# VS1005BOB-Pico-LCD_2024-06-08.net
KiCad netlist of a schematic drawn in Altium Designer
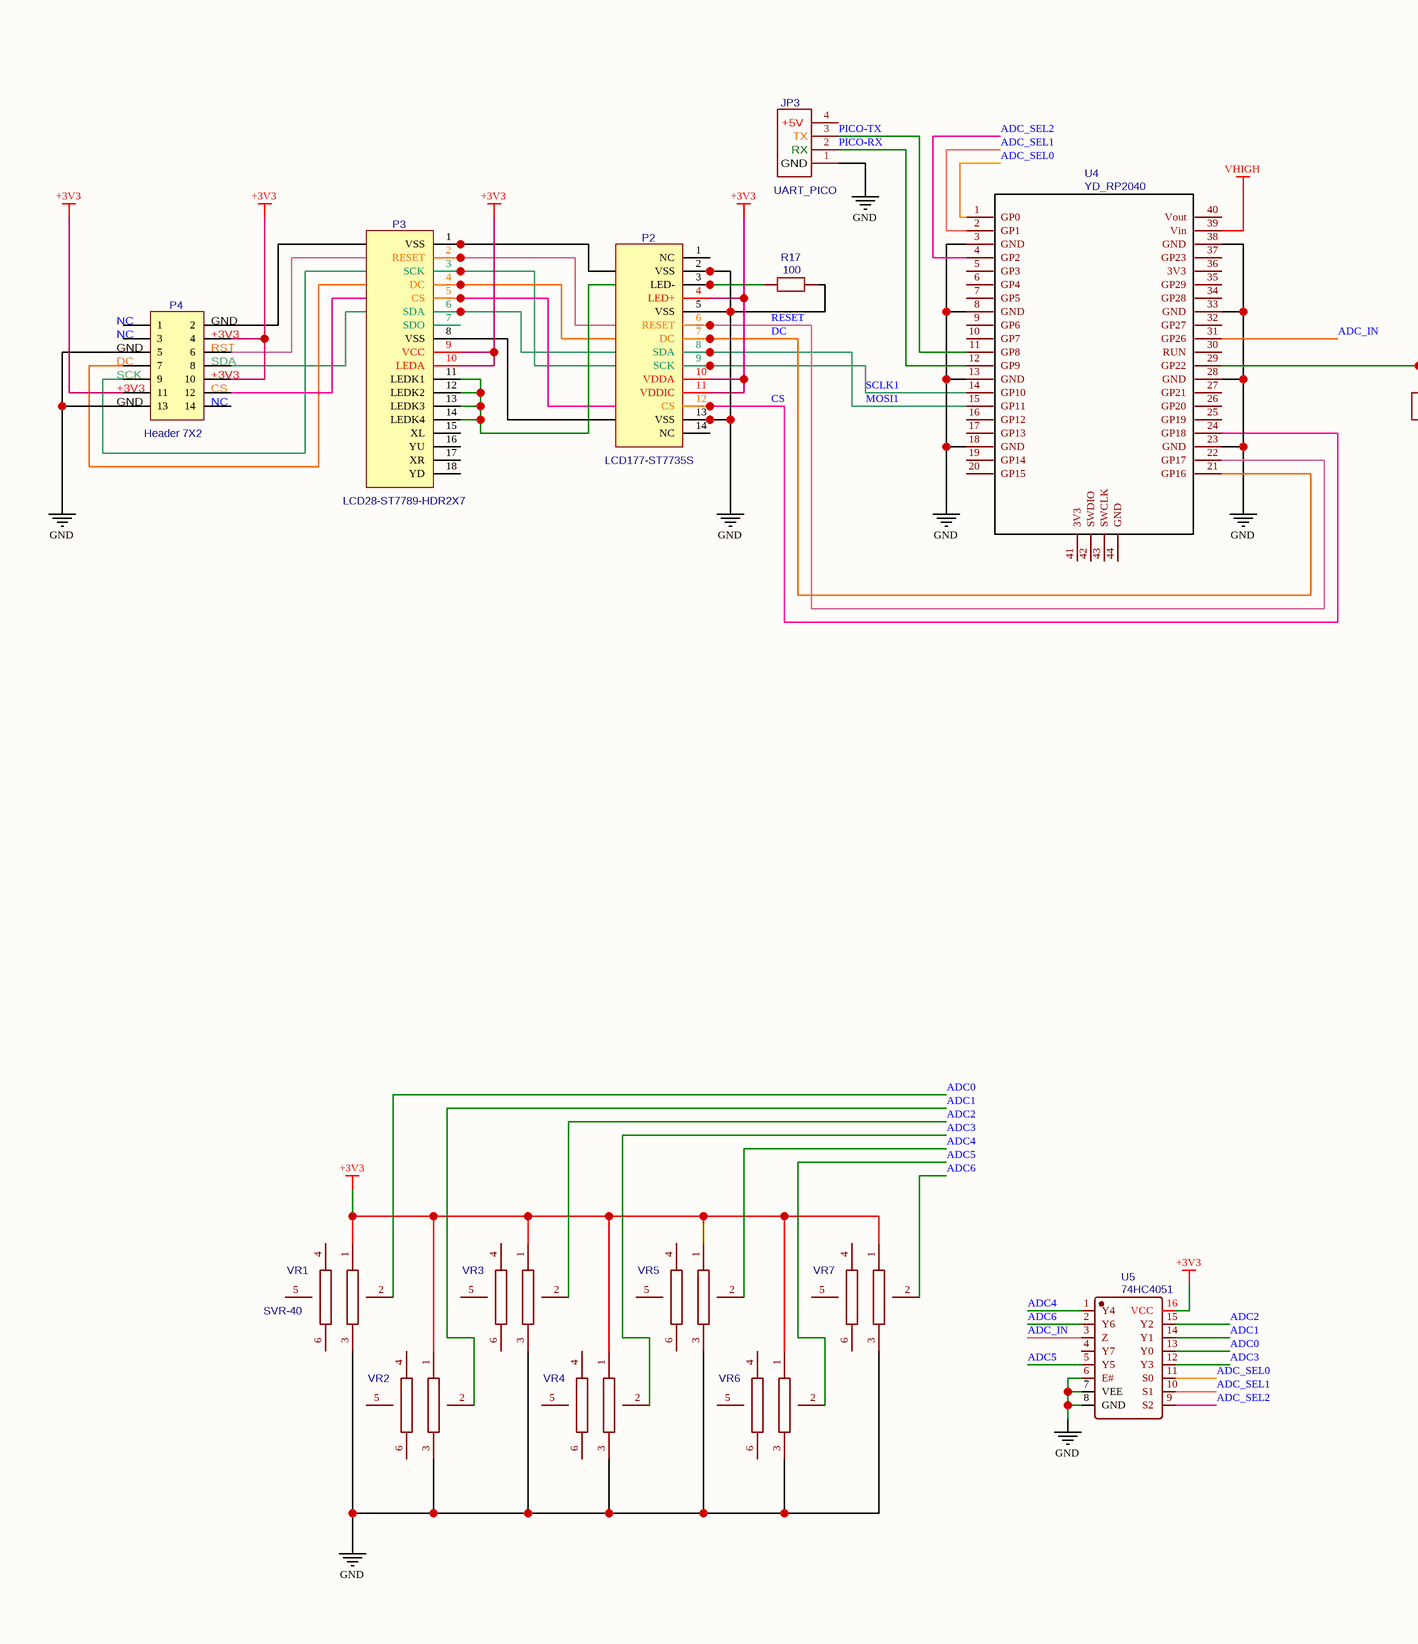
[diagram p0: VS1005BOB-Pico-LCD_2024-06-08.schdoc, left]
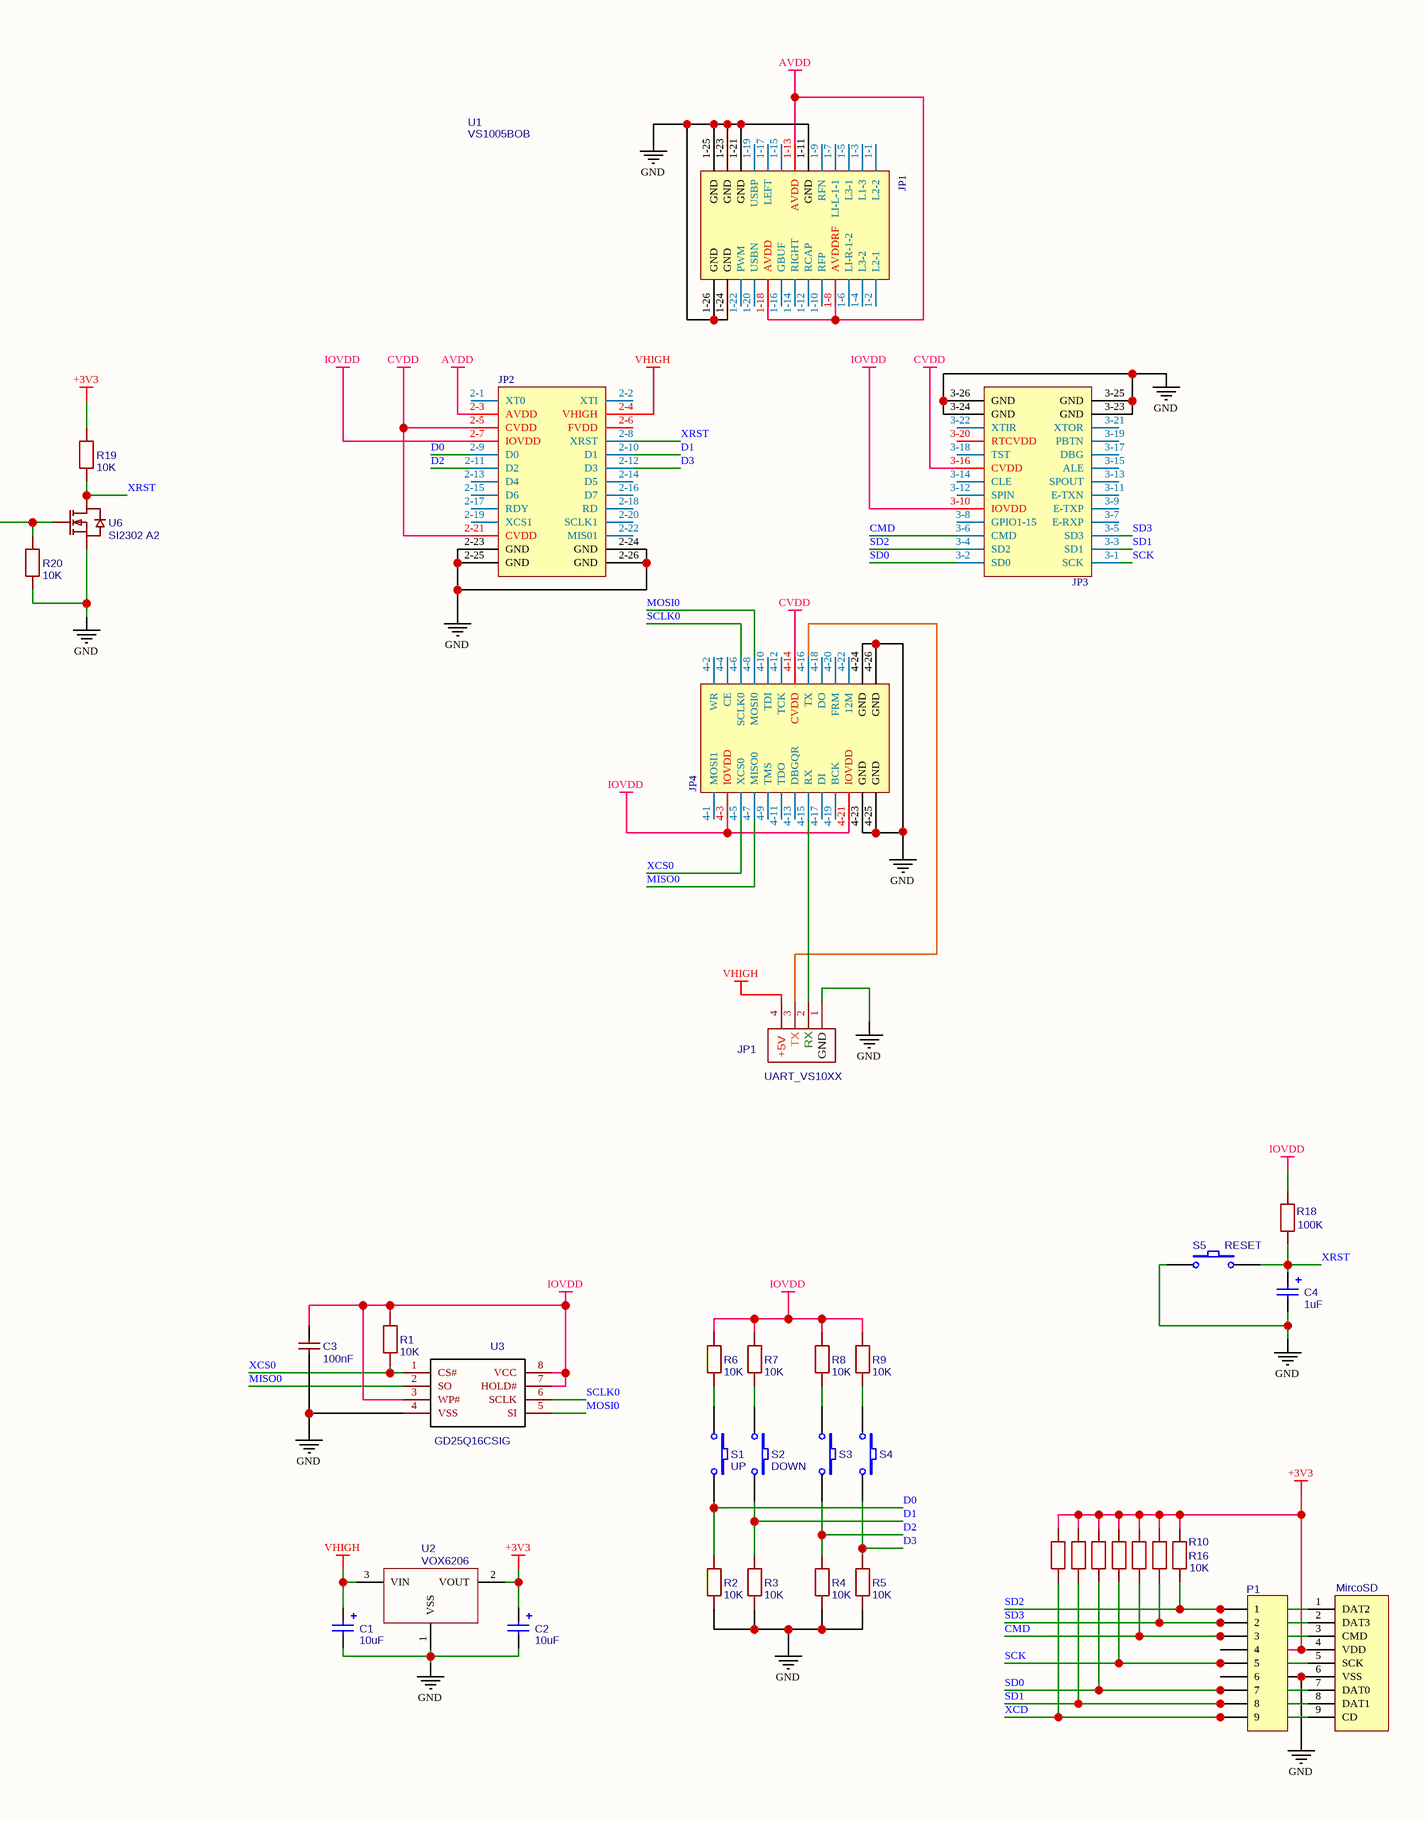
[diagram p1: VS1005BOB-Pico-LCD_2024-06-08.schdoc, right]

(export (version "E")
  (design (tool "Eeschema 10.0.6"))
  (components
    (comp (ref "C1")
      (value "10uF")
      (fields (field (name "PUBLISHER") "Altium Limited") (field (name "CONTRIBUTOR") "kmok163"))
      (libsource (lib "altium-import") (part "root_0_10uF_"))
    )
    (comp (ref "C2")
      (value "10uF")
      (fields (field (name "PUBLISHER") "Altium Limited") (field (name "CONTRIBUTOR") "kmok163"))
      (libsource (lib "altium-import") (part "root_0_10uF_"))
    )
    (comp (ref "C3")
      (value "100nF")
      (fields
        (field (name "MANUFACTURER PART") "CC0805KRX7R9BB104")
        (field (name "MANUFACTURER") "YAGEO")
        (field (name "CONTRIBUTOR") "fen-1")
      )
      (libsource (lib "altium-import") (part "root_3_100nF_"))
    )
    (comp (ref "C4")
      (value "1uF")
      (fields (field (name "PUBLISHER") "Altium Limited") (field (name "CONTRIBUTOR") "kmok163"))
      (libsource (lib "altium-import") (part "root_0_1uF_"))
    )
    (comp (ref "JP1")
      (value "UART_VS10XX")
      (description "Header 4")
      (fields (field (name "CONTRIBUTOR") "SparkFun"))
      (libsource (lib "altium-import") (part "root_1_UART_VS10XX_"))
    )
    (comp (ref "JP3")
      (value "UART_PICO")
      (description "Header 4")
      (fields (field (name "CONTRIBUTOR") "SparkFun"))
      (libsource (lib "altium-import") (part "root_0_UART_PICO_"))
    )
    (comp (ref "P1")
      (value "Header 9")
      (fields (field (name "PUBLISHER") "Altium Limited") (field (name "CONTRIBUTOR") "kmok163"))
      (libsource (lib "altium-import") (part "root_0_Header 9_"))
    )
    (comp (ref "P2")
      (value "LCD177-ST7735S")
      (fields (field (name "PUBLISHER") "Altium Limited") (field (name "CONTRIBUTOR") "kmok163"))
      (libsource (lib "altium-import") (part "root_0_LCD177-ST7735S_"))
    )
    (comp (ref "P3")
      (value "LCD28-ST7789-HDR2X7")
      (fields (field (name "PUBLISHER") "Altium Limited") (field (name "CONTRIBUTOR") "kmok163"))
      (libsource (lib "altium-import") (part "root_0_LCD28-ST7789-HDR2X7_"))
    )
    (comp (ref "P4")
      (value "Header 7X2")
      (fields (field (name "PUBLISHER") "Altium Limited") (field (name "CONTRIBUTOR") "lingtian"))
      (libsource (lib "altium-import") (part "root_0_Header 7X2_"))
    )
    (comp (ref "P6")
      (value "MircoSD")
      (fields (field (name "PUBLISHER") "Altium Limited") (field (name "CONTRIBUTOR") "kmok163"))
      (libsource (lib "altium-import") (part "root_0_MircoSD_"))
    )
    (comp (ref "R1")
      (value "10K")
      (fields (field (name "CONTRIBUTOR") "EDAUSER001"))
      (libsource (lib "altium-import") (part "root_1_10K_"))
    )
    (comp (ref "R2")
      (value "10K")
      (fields (field (name "CONTRIBUTOR") "EDAUSER001"))
      (libsource (lib "altium-import") (part "root_1_10K_"))
    )
    (comp (ref "R3")
      (value "10K")
      (fields (field (name "CONTRIBUTOR") "EDAUSER001"))
      (libsource (lib "altium-import") (part "root_1_10K_"))
    )
    (comp (ref "R4")
      (value "10K")
      (fields (field (name "CONTRIBUTOR") "EDAUSER001"))
      (libsource (lib "altium-import") (part "root_1_10K_"))
    )
    (comp (ref "R5")
      (value "10K")
      (fields (field (name "CONTRIBUTOR") "EDAUSER001"))
      (libsource (lib "altium-import") (part "root_1_10K_"))
    )
    (comp (ref "R6")
      (value "10K")
      (fields (field (name "CONTRIBUTOR") "EDAUSER001"))
      (libsource (lib "altium-import") (part "root_1_10K_"))
    )
    (comp (ref "R7")
      (value "10K")
      (fields (field (name "CONTRIBUTOR") "EDAUSER001"))
      (libsource (lib "altium-import") (part "root_1_10K_"))
    )
    (comp (ref "R8")
      (value "10K")
      (fields (field (name "CONTRIBUTOR") "EDAUSER001"))
      (libsource (lib "altium-import") (part "root_1_10K_"))
    )
    (comp (ref "R9")
      (value "10K")
      (fields (field (name "CONTRIBUTOR") "EDAUSER001"))
      (libsource (lib "altium-import") (part "root_1_10K_"))
    )
    (comp (ref "R10")
      (value "10K")
      (fields (field (name "CONTRIBUTOR") "EDAUSER001"))
      (libsource (lib "altium-import") (part "root_1_10K_"))
    )
    (comp (ref "R11")
      (value "10K")
      (fields (field (name "CONTRIBUTOR") "EDAUSER001"))
      (libsource (lib "altium-import") (part "root_1_10K_"))
    )
    (comp (ref "R12")
      (value "10K")
      (fields (field (name "CONTRIBUTOR") "EDAUSER001"))
      (libsource (lib "altium-import") (part "root_1_10K_"))
    )
    (comp (ref "R13")
      (value "10K")
      (fields (field (name "CONTRIBUTOR") "EDAUSER001"))
      (libsource (lib "altium-import") (part "root_1_10K_"))
    )
    (comp (ref "R14")
      (value "10K")
      (fields (field (name "CONTRIBUTOR") "EDAUSER001"))
      (libsource (lib "altium-import") (part "root_1_10K_"))
    )
    (comp (ref "R15")
      (value "10K")
      (fields (field (name "CONTRIBUTOR") "EDAUSER001"))
      (libsource (lib "altium-import") (part "root_1_10K_"))
    )
    (comp (ref "R16")
      (value "10K")
      (fields (field (name "CONTRIBUTOR") "EDAUSER001"))
      (libsource (lib "altium-import") (part "root_1_10K_"))
    )
    (comp (ref "R17")
      (value "100")
      (fields (field (name "CONTRIBUTOR") "EDAUSER001"))
      (libsource (lib "altium-import") (part "root_0_100_"))
    )
    (comp (ref "R18")
      (value "100K")
      (fields (field (name "CONTRIBUTOR") "EDAUSER001"))
      (libsource (lib "altium-import") (part "root_1_100K_"))
    )
    (comp (ref "R19")
      (value "10K")
      (fields (field (name "CONTRIBUTOR") "EDAUSER001"))
      (libsource (lib "altium-import") (part "root_1_10K_"))
    )
    (comp (ref "R20")
      (value "10K")
      (fields (field (name "CONTRIBUTOR") "EDAUSER001"))
      (libsource (lib "altium-import") (part "root_1_10K_"))
    )
    (comp (ref "S1")
      (value "UP")
      (fields (field (name "PUBLISHER") "Altium Limited") (field (name "CONTRIBUTOR") "kmok163"))
      (libsource (lib "altium-import") (part "root_3_UP_"))
    )
    (comp (ref "S2")
      (value "DOWN")
      (fields (field (name "PUBLISHER") "Altium Limited") (field (name "CONTRIBUTOR") "kmok163"))
      (libsource (lib "altium-import") (part "root_3_DOWN_"))
    )
    (comp (ref "S3")
      (value "D2")
      (fields (field (name "PUBLISHER") "Altium Limited") (field (name "CONTRIBUTOR") "kmok163"))
      (libsource (lib "altium-import") (part "root_3_D2_"))
    )
    (comp (ref "S4")
      (value "D3")
      (fields (field (name "PUBLISHER") "Altium Limited") (field (name "CONTRIBUTOR") "kmok163"))
      (libsource (lib "altium-import") (part "root_3_D3_"))
    )
    (comp (ref "S5")
      (value "RESET")
      (fields (field (name "PUBLISHER") "Altium Limited") (field (name "CONTRIBUTOR") "kmok163"))
      (libsource (lib "altium-import") (part "root_0_RESET_"))
    )
    (comp (ref "U1")
      (value "VS1005BOB")
      (fields (field (name "MANUFACTURER") "VLSI Solution Oy") (field (name "CONTRIBUTOR") "kmok163"))
      (libsource (lib "altium-import") (part "root_0_VS1005BOB_"))
    )
    (comp (ref "U2")
      (value "VOX6206")
      (fields (field (name "PUBLISHER") "Altium Limited") (field (name "CONTRIBUTOR") "kmok163"))
      (libsource (lib "altium-import") (part "root_0_VOX6206_"))
    )
    (comp (ref "U3")
      (value "GD25Q16CSIG")
      (fields (field (name "MANUFACTURER") "GigaDevice(兆易创新)"))
      (libsource (lib "altium-import") (part "root_0_GD25Q16CSIG_"))
    )
    (comp (ref "U4")
      (value "YD_RP2040")
      (fields (field (name "CONTRIBUTOR") "armxu"))
      (libsource (lib "altium-import") (part "root_0_YD_RP2040_"))
    )
    (comp (ref "U5")
      (value "74HC4051")
      (fields (field (name "MANUFACTURER") "I-CORE(中微爱芯)") (field (name "CONTRIBUTOR") "lcsc"))
      (libsource (lib "altium-import") (part "root_0_74HC4051_"))
    )
    (comp (ref "U6")
      (value "SI2302 A2")
      (fields (field (name "MANUFACTURER") "YONGYUTAI(永裕泰)") (field (name "CONTRIBUTOR") "lcsc"))
      (libsource (lib "altium-import") (part "root_0_SI2302 A2_"))
    )
    (comp (ref "VR1")
      (value "SVR-40")
      (fields
        (field (name "MANUFACTURER") "联合科技")
        (field (name "MANUFACTURER PART") "VVR-40-100KB")
        (field (name "CONTRIBUTOR") "kmok163")
      )
      (libsource (lib "altium-import") (part "root_0_SVR-40_"))
    )
    (comp (ref "VR2")
      (value "SVR-40")
      (fields
        (field (name "MANUFACTURER") "联合科技")
        (field (name "MANUFACTURER PART") "VVR-40-100KB")
        (field (name "CONTRIBUTOR") "kmok163")
      )
      (libsource (lib "altium-import") (part "root_0_SVR-40_"))
    )
    (comp (ref "VR3")
      (value "SVR-40")
      (fields
        (field (name "MANUFACTURER") "联合科技")
        (field (name "MANUFACTURER PART") "VVR-40-100KB")
        (field (name "CONTRIBUTOR") "kmok163")
      )
      (libsource (lib "altium-import") (part "root_0_SVR-40_"))
    )
    (comp (ref "VR4")
      (value "SVR-40")
      (fields
        (field (name "MANUFACTURER") "联合科技")
        (field (name "MANUFACTURER PART") "VVR-40-100KB")
        (field (name "CONTRIBUTOR") "kmok163")
      )
      (libsource (lib "altium-import") (part "root_0_SVR-40_"))
    )
    (comp (ref "VR5")
      (value "SVR-40")
      (fields
        (field (name "MANUFACTURER") "联合科技")
        (field (name "MANUFACTURER PART") "VVR-40-100KB")
        (field (name "CONTRIBUTOR") "kmok163")
      )
      (libsource (lib "altium-import") (part "root_0_SVR-40_"))
    )
    (comp (ref "VR6")
      (value "SVR-40")
      (fields
        (field (name "MANUFACTURER") "联合科技")
        (field (name "MANUFACTURER PART") "VVR-40-100KB")
        (field (name "CONTRIBUTOR") "kmok163")
      )
      (libsource (lib "altium-import") (part "root_0_SVR-40_"))
    )
    (comp (ref "VR7")
      (value "SVR-40")
      (fields
        (field (name "MANUFACTURER") "联合科技")
        (field (name "MANUFACTURER PART") "VVR-40-100KB")
        (field (name "CONTRIBUTOR") "kmok163")
      )
      (libsource (lib "altium-import") (part "root_0_SVR-40_"))
    )
  )
  (nets
    (net (code "1") (name "+3V3") (class "Default")
      (node (ref "C2") (pin "1") (pinfunction "1_1") (pintype "passive"))
      (node (ref "P1") (pin "4") (pinfunction "4_4") (pintype "passive"))
      (node (ref "P2") (pin "10") (pinfunction "VDDA_10") (pintype "passive"))
      (node (ref "P2") (pin "11") (pinfunction "VDDIC_11") (pintype "passive"))
      (node (ref "P2") (pin "4") (pinfunction "LED+_4") (pintype "passive"))
      (node (ref "P3") (pin "10") (pinfunction "LEDA_10") (pintype "passive"))
      (node (ref "P3") (pin "9") (pinfunction "VCC_9") (pintype "passive"))
      (node (ref "P4") (pin "10") (pinfunction "10_10") (pintype "passive"))
      (node (ref "P4") (pin "11") (pinfunction "11_11") (pintype "passive"))
      (node (ref "P4") (pin "4") (pinfunction "4_4") (pintype "passive"))
      (node (ref "P6") (pin "4") (pinfunction "VDD_4") (pintype "passive"))
      (node (ref "R10") (pin "2") (pinfunction "2_2") (pintype "passive"))
      (node (ref "R11") (pin "2") (pinfunction "2_2") (pintype "passive"))
      (node (ref "R12") (pin "2") (pinfunction "2_2") (pintype "passive"))
      (node (ref "R13") (pin "2") (pinfunction "2_2") (pintype "passive"))
      (node (ref "R14") (pin "2") (pinfunction "2_2") (pintype "passive"))
      (node (ref "R15") (pin "2") (pinfunction "2_2") (pintype "passive"))
      (node (ref "R16") (pin "2") (pinfunction "2_2") (pintype "passive"))
      (node (ref "R19") (pin "2") (pinfunction "2_2") (pintype "passive"))
      (node (ref "U2") (pin "2") (pinfunction "VOUT_2") (pintype "passive"))
      (node (ref "U5") (pin "16") (pinfunction "VCC_16") (pintype "passive"))
      (node (ref "VR1") (pin "1") (pinfunction "1_1") (pintype "passive"))
      (node (ref "VR2") (pin "1") (pinfunction "1_1") (pintype "passive"))
      (node (ref "VR3") (pin "1") (pinfunction "1_1") (pintype "passive"))
      (node (ref "VR4") (pin "1") (pinfunction "1_1") (pintype "passive"))
      (node (ref "VR5") (pin "1") (pinfunction "1_1") (pintype "passive"))
      (node (ref "VR6") (pin "1") (pinfunction "1_1") (pintype "passive"))
      (node (ref "VR7") (pin "1") (pinfunction "1_1") (pintype "passive"))
    )
    (net (code "2") (name "/ADC0") (class "Default")
      (node (ref "U5") (pin "13") (pinfunction "Y0_13") (pintype "passive"))
      (node (ref "VR1") (pin "2") (pinfunction "2_2") (pintype "passive"))
    )
    (net (code "3") (name "/ADC1") (class "Default")
      (node (ref "U5") (pin "14") (pinfunction "Y1_14") (pintype "passive"))
      (node (ref "VR2") (pin "2") (pinfunction "2_2") (pintype "passive"))
    )
    (net (code "4") (name "/ADC2") (class "Default")
      (node (ref "U5") (pin "15") (pinfunction "Y2_15") (pintype "passive"))
      (node (ref "VR3") (pin "2") (pinfunction "2_2") (pintype "passive"))
    )
    (net (code "5") (name "/ADC3") (class "Default")
      (node (ref "U5") (pin "12") (pinfunction "Y3_12") (pintype "passive"))
      (node (ref "VR4") (pin "2") (pinfunction "2_2") (pintype "passive"))
    )
    (net (code "6") (name "/ADC4") (class "Default")
      (node (ref "U5") (pin "1") (pinfunction "Y4_1") (pintype "passive"))
      (node (ref "VR5") (pin "2") (pinfunction "2_2") (pintype "passive"))
    )
    (net (code "7") (name "/ADC5") (class "Default")
      (node (ref "U5") (pin "5") (pinfunction "Y5_5") (pintype "passive"))
      (node (ref "VR6") (pin "2") (pinfunction "2_2") (pintype "passive"))
    )
    (net (code "8") (name "/ADC6") (class "Default")
      (node (ref "U5") (pin "2") (pinfunction "Y6_2") (pintype "passive"))
      (node (ref "VR7") (pin "2") (pinfunction "2_2") (pintype "passive"))
    )
    (net (code "9") (name "/ADC_IN") (class "Default")
      (node (ref "U4") (pin "31") (pinfunction "GP26_31") (pintype "passive"))
      (node (ref "U5") (pin "3") (pinfunction "Z_3") (pintype "passive"))
    )
    (net (code "10") (name "/ADC_SEL0") (class "Default")
      (node (ref "U4") (pin "1") (pinfunction "GP0_1") (pintype "passive"))
      (node (ref "U5") (pin "11") (pinfunction "S0_11") (pintype "passive"))
    )
    (net (code "11") (name "/ADC_SEL1") (class "Default")
      (node (ref "U4") (pin "2") (pinfunction "GP1_2") (pintype "passive"))
      (node (ref "U5") (pin "10") (pinfunction "S1_10") (pintype "passive"))
    )
    (net (code "12") (name "/ADC_SEL2") (class "Default")
      (node (ref "U4") (pin "4") (pinfunction "GP2_4") (pintype "passive"))
      (node (ref "U5") (pin "9") (pinfunction "S2_9") (pintype "passive"))
    )
    (net (code "13") (name "/CMD") (class "Default")
      (node (ref "P1") (pin "3") (pinfunction "3_3") (pintype "passive"))
      (node (ref "P6") (pin "3") (pinfunction "CMD_3") (pintype "passive"))
      (node (ref "R14") (pin "1") (pinfunction "1_1") (pintype "passive"))
      (node (ref "U1") (pin "3-6") (pinfunction "CMD_3-6") (pintype "passive"))
    )
    (net (code "14") (name "/CS") (class "Default")
      (node (ref "P2") (pin "12") (pinfunction "CS_12") (pintype "passive"))
      (node (ref "P3") (pin "5") (pinfunction "CS_5") (pintype "passive"))
      (node (ref "P4") (pin "12") (pinfunction "12_12") (pintype "passive"))
      (node (ref "U4") (pin "24") (pinfunction "GP18_24") (pintype "passive"))
    )
    (net (code "15") (name "/D0") (class "Default")
      (node (ref "R2") (pin "2") (pinfunction "2_2") (pintype "passive"))
      (node (ref "S1") (pin "2") (pinfunction "2_2") (pintype "passive"))
      (node (ref "U1") (pin "2-9") (pinfunction "D0_2-9") (pintype "passive"))
    )
    (net (code "16") (name "/D1") (class "Default")
      (node (ref "R3") (pin "2") (pinfunction "2_2") (pintype "passive"))
      (node (ref "S2") (pin "2") (pinfunction "2_2") (pintype "passive"))
      (node (ref "U1") (pin "2-10") (pinfunction "D1_2-10") (pintype "passive"))
    )
    (net (code "17") (name "/D2") (class "Default")
      (node (ref "R4") (pin "2") (pinfunction "2_2") (pintype "passive"))
      (node (ref "S3") (pin "2") (pinfunction "2_2") (pintype "passive"))
      (node (ref "U1") (pin "2-11") (pinfunction "D2_2-11") (pintype "passive"))
    )
    (net (code "18") (name "/D3") (class "Default")
      (node (ref "R5") (pin "2") (pinfunction "2_2") (pintype "passive"))
      (node (ref "S4") (pin "2") (pinfunction "2_2") (pintype "passive"))
      (node (ref "U1") (pin "2-12") (pinfunction "D3_2-12") (pintype "passive"))
    )
    (net (code "19") (name "/DC") (class "Default")
      (node (ref "P2") (pin "7") (pinfunction "DC_7") (pintype "passive"))
      (node (ref "P3") (pin "4") (pinfunction "DC_4") (pintype "passive"))
      (node (ref "P4") (pin "7") (pinfunction "7_7") (pintype "passive"))
      (node (ref "U4") (pin "21") (pinfunction "GP16_21") (pintype "passive"))
    )
    (net (code "20") (name "/MISO0") (class "Default")
      (node (ref "U1") (pin "4-7") (pinfunction "MISO0_4-7") (pintype "passive"))
      (node (ref "U3") (pin "2") (pinfunction "SO_2") (pintype "passive"))
    )
    (net (code "21") (name "/MOSI0") (class "Default")
      (node (ref "U1") (pin "4-8") (pinfunction "MOSI0_4-8") (pintype "passive"))
      (node (ref "U3") (pin "5") (pinfunction "SI_5") (pintype "passive"))
    )
    (net (code "22") (name "/MOSI1") (class "Default")
      (node (ref "P2") (pin "8") (pinfunction "SDA_8") (pintype "passive"))
      (node (ref "P3") (pin "6") (pinfunction "SDA_6") (pintype "passive"))
      (node (ref "P4") (pin "8") (pinfunction "8_8") (pintype "passive"))
      (node (ref "U4") (pin "15") (pinfunction "GP11_15") (pintype "passive"))
    )
    (net (code "23") (name "/PICO-RX") (class "Default")
      (node (ref "JP3") (pin "2") (pinfunction "2_2") (pintype "passive"))
      (node (ref "U4") (pin "12") (pinfunction "GP9_12") (pintype "passive"))
    )
    (net (code "24") (name "/PICO-TX") (class "Default")
      (node (ref "JP3") (pin "3") (pinfunction "3_3") (pintype "passive"))
      (node (ref "U4") (pin "11") (pinfunction "GP8_11") (pintype "passive"))
    )
    (net (code "25") (name "/RESET") (class "Default")
      (node (ref "P2") (pin "6") (pinfunction "RESET_6") (pintype "passive"))
      (node (ref "P3") (pin "2") (pinfunction "RESET_2") (pintype "passive"))
      (node (ref "P4") (pin "6") (pinfunction "6_6") (pintype "passive"))
      (node (ref "U4") (pin "22") (pinfunction "GP17_22") (pintype "passive"))
    )
    (net (code "26") (name "/SCK") (class "Default")
      (node (ref "P1") (pin "5") (pinfunction "5_5") (pintype "passive"))
      (node (ref "P6") (pin "5") (pinfunction "SCK_5") (pintype "passive"))
      (node (ref "R13") (pin "1") (pinfunction "1_1") (pintype "passive"))
      (node (ref "U1") (pin "3-1") (pinfunction "SCK_3-1") (pintype "passive"))
    )
    (net (code "27") (name "/SCLK0") (class "Default")
      (node (ref "U1") (pin "4-6") (pinfunction "SCLK0_4-6") (pintype "passive"))
      (node (ref "U3") (pin "6") (pinfunction "SCLK_6") (pintype "passive"))
    )
    (net (code "28") (name "/SCLK1") (class "Default")
      (node (ref "P2") (pin "9") (pinfunction "SCK_9") (pintype "passive"))
      (node (ref "P3") (pin "3") (pinfunction "SCK_3") (pintype "passive"))
      (node (ref "P4") (pin "9") (pinfunction "9_9") (pintype "passive"))
      (node (ref "U4") (pin "14") (pinfunction "GP10_14") (pintype "passive"))
    )
    (net (code "29") (name "/SD0") (class "Default")
      (node (ref "P1") (pin "7") (pinfunction "7_7") (pintype "passive"))
      (node (ref "P6") (pin "7") (pinfunction "DAT0_7") (pintype "passive"))
      (node (ref "R12") (pin "1") (pinfunction "1_1") (pintype "passive"))
      (node (ref "U1") (pin "3-2") (pinfunction "SD0_3-2") (pintype "passive"))
    )
    (net (code "30") (name "/SD1") (class "Default")
      (node (ref "P1") (pin "8") (pinfunction "8_8") (pintype "passive"))
      (node (ref "P6") (pin "8") (pinfunction "DAT1_8") (pintype "passive"))
      (node (ref "R11") (pin "1") (pinfunction "1_1") (pintype "passive"))
      (node (ref "U1") (pin "3-3") (pinfunction "SD1_3-3") (pintype "passive"))
    )
    (net (code "31") (name "/SD2") (class "Default")
      (node (ref "P1") (pin "1") (pinfunction "1_1") (pintype "passive"))
      (node (ref "P6") (pin "1") (pinfunction "DAT2_1") (pintype "passive"))
      (node (ref "R16") (pin "1") (pinfunction "1_1") (pintype "passive"))
      (node (ref "U1") (pin "3-4") (pinfunction "SD2_3-4") (pintype "passive"))
    )
    (net (code "32") (name "/SD3") (class "Default")
      (node (ref "P1") (pin "2") (pinfunction "2_2") (pintype "passive"))
      (node (ref "P6") (pin "2") (pinfunction "DAT3_2") (pintype "passive"))
      (node (ref "R15") (pin "1") (pinfunction "1_1") (pintype "passive"))
      (node (ref "U1") (pin "3-5") (pinfunction "SD3_3-5") (pintype "passive"))
    )
    (net (code "33") (name "/XCD") (class "Default")
      (node (ref "P1") (pin "9") (pinfunction "9_9") (pintype "passive"))
      (node (ref "P6") (pin "9") (pinfunction "CD_9") (pintype "passive"))
      (node (ref "R10") (pin "1") (pinfunction "1_1") (pintype "passive"))
    )
    (net (code "34") (name "/XCS0") (class "Default")
      (node (ref "R1") (pin "1") (pinfunction "1_1") (pintype "passive"))
      (node (ref "U1") (pin "4-5") (pinfunction "XCS0_4-5") (pintype "passive"))
      (node (ref "U3") (pin "1") (pinfunction "CS#_1") (pintype "passive"))
    )
    (net (code "35") (name "/XRST") (class "Default")
      (node (ref "C4") (pin "1") (pinfunction "1_1") (pintype "passive"))
      (node (ref "R18") (pin "1") (pinfunction "1_1") (pintype "passive"))
      (node (ref "R19") (pin "1") (pinfunction "1_1") (pintype "passive"))
      (node (ref "S5") (pin "2") (pinfunction "2_2") (pintype "passive"))
      (node (ref "U1") (pin "2-8") (pinfunction "XRST_2-8") (pintype "passive"))
      (node (ref "U6") (pin "3") (pinfunction "D_3") (pintype "passive"))
    )
    (net (code "36") (name "AVDD") (class "Default")
      (node (ref "U1") (pin "1-13") (pinfunction "AVDD_1-13") (pintype "passive"))
      (node (ref "U1") (pin "1-18") (pinfunction "AVDD_1-18") (pintype "passive"))
      (node (ref "U1") (pin "1-8") (pinfunction "AVDDRF_1-8") (pintype "passive"))
      (node (ref "U1") (pin "2-3") (pinfunction "AVDD_2-3") (pintype "passive"))
    )
    (net (code "37") (name "CVDD") (class "Default")
      (node (ref "U1") (pin "2-21") (pinfunction "CVDD_2-21") (pintype "passive"))
      (node (ref "U1") (pin "2-5") (pinfunction "CVDD_2-5") (pintype "passive"))
      (node (ref "U1") (pin "3-16") (pinfunction "CVDD_3-16") (pintype "passive"))
      (node (ref "U1") (pin "4-14") (pinfunction "CVDD_4-14") (pintype "passive"))
    )
    (net (code "38") (name "GND") (class "Default")
      (node (ref "C1") (pin "2") (pinfunction "2_2") (pintype "passive"))
      (node (ref "C2") (pin "2") (pinfunction "2_2") (pintype "passive"))
      (node (ref "C3") (pin "2") (pinfunction "2_2") (pintype "passive"))
      (node (ref "C4") (pin "2") (pinfunction "2_2") (pintype "passive"))
      (node (ref "JP1") (pin "1") (pinfunction "1_1") (pintype "passive"))
      (node (ref "JP3") (pin "1") (pinfunction "1_1") (pintype "passive"))
      (node (ref "P1") (pin "6") (pinfunction "6_6") (pintype "passive"))
      (node (ref "P2") (pin "13") (pinfunction "VSS_13") (pintype "passive"))
      (node (ref "P2") (pin "2") (pinfunction "VSS_2") (pintype "passive"))
      (node (ref "P2") (pin "5") (pinfunction "VSS_5") (pintype "passive"))
      (node (ref "P3") (pin "1") (pinfunction "VSS_1") (pintype "passive"))
      (node (ref "P3") (pin "8") (pinfunction "VSS_8") (pintype "passive"))
      (node (ref "P4") (pin "13") (pinfunction "13_13") (pintype "passive"))
      (node (ref "P4") (pin "2") (pinfunction "2_2") (pintype "passive"))
      (node (ref "P4") (pin "5") (pinfunction "5_5") (pintype "passive"))
      (node (ref "P6") (pin "6") (pinfunction "VSS_6") (pintype "passive"))
      (node (ref "R17") (pin "1") (pinfunction "1_1") (pintype "passive"))
      (node (ref "R2") (pin "1") (pinfunction "1_1") (pintype "passive"))
      (node (ref "R20") (pin "1") (pinfunction "1_1") (pintype "passive"))
      (node (ref "R3") (pin "1") (pinfunction "1_1") (pintype "passive"))
      (node (ref "R4") (pin "1") (pinfunction "1_1") (pintype "passive"))
      (node (ref "R5") (pin "1") (pinfunction "1_1") (pintype "passive"))
      (node (ref "S5") (pin "1") (pinfunction "1_1") (pintype "passive"))
      (node (ref "U1") (pin "1-11") (pinfunction "GND_1-11") (pintype "passive"))
      (node (ref "U1") (pin "1-21") (pinfunction "GND_1-21") (pintype "passive"))
      (node (ref "U1") (pin "1-23") (pinfunction "GND_1-23") (pintype "passive"))
      (node (ref "U1") (pin "1-24") (pinfunction "GND_1-24") (pintype "passive"))
      (node (ref "U1") (pin "1-25") (pinfunction "GND_1-25") (pintype "passive"))
      (node (ref "U1") (pin "1-26") (pinfunction "GND_1-26") (pintype "passive"))
      (node (ref "U1") (pin "2-23") (pinfunction "GND_2-23") (pintype "passive"))
      (node (ref "U1") (pin "2-24") (pinfunction "GND_2-24") (pintype "passive"))
      (node (ref "U1") (pin "2-25") (pinfunction "GND_2-25") (pintype "passive"))
      (node (ref "U1") (pin "2-26") (pinfunction "GND_2-26") (pintype "passive"))
      (node (ref "U1") (pin "3-23") (pinfunction "GND_3-23") (pintype "passive"))
      (node (ref "U1") (pin "3-24") (pinfunction "GND_3-24") (pintype "passive"))
      (node (ref "U1") (pin "3-25") (pinfunction "GND_3-25") (pintype "passive"))
      (node (ref "U1") (pin "3-26") (pinfunction "GND_3-26") (pintype "passive"))
      (node (ref "U1") (pin "4-23") (pinfunction "GND_4-23") (pintype "passive"))
      (node (ref "U1") (pin "4-24") (pinfunction "GND_4-24") (pintype "passive"))
      (node (ref "U1") (pin "4-25") (pinfunction "GND_4-25") (pintype "passive"))
      (node (ref "U1") (pin "4-26") (pinfunction "GND_4-26") (pintype "passive"))
      (node (ref "U2") (pin "1") (pinfunction "VSS_1") (pintype "passive"))
      (node (ref "U3") (pin "4") (pinfunction "VSS_4") (pintype "passive"))
      (node (ref "U4") (pin "13") (pinfunction "GND_13") (pintype "passive"))
      (node (ref "U4") (pin "18") (pinfunction "GND_18") (pintype "passive"))
      (node (ref "U4") (pin "23") (pinfunction "GND_23") (pintype "passive"))
      (node (ref "U4") (pin "28") (pinfunction "GND_28") (pintype "passive"))
      (node (ref "U4") (pin "3") (pinfunction "GND_3") (pintype "passive"))
      (node (ref "U4") (pin "33") (pinfunction "GND_33") (pintype "passive"))
      (node (ref "U4") (pin "38") (pinfunction "GND_38") (pintype "passive"))
      (node (ref "U4") (pin "8") (pinfunction "GND_8") (pintype "passive"))
      (node (ref "U5") (pin "6") (pinfunction "E#_6") (pintype "passive"))
      (node (ref "U5") (pin "7") (pinfunction "VEE_7") (pintype "passive"))
      (node (ref "U5") (pin "8") (pinfunction "GND_8") (pintype "passive"))
      (node (ref "U6") (pin "2") (pinfunction "S_2") (pintype "passive"))
      (node (ref "VR1") (pin "3") (pinfunction "3_3") (pintype "passive"))
      (node (ref "VR2") (pin "3") (pinfunction "3_3") (pintype "passive"))
      (node (ref "VR3") (pin "3") (pinfunction "3_3") (pintype "passive"))
      (node (ref "VR4") (pin "3") (pinfunction "3_3") (pintype "passive"))
      (node (ref "VR5") (pin "3") (pinfunction "3_3") (pintype "passive"))
      (node (ref "VR6") (pin "3") (pinfunction "3_3") (pintype "passive"))
      (node (ref "VR7") (pin "3") (pinfunction "3_3") (pintype "passive"))
    )
    (net (code "39") (name "IOVDD") (class "Default")
      (node (ref "C3") (pin "1") (pinfunction "1_1") (pintype "passive"))
      (node (ref "R1") (pin "2") (pinfunction "2_2") (pintype "passive"))
      (node (ref "R18") (pin "2") (pinfunction "2_2") (pintype "passive"))
      (node (ref "R6") (pin "2") (pinfunction "2_2") (pintype "passive"))
      (node (ref "R7") (pin "2") (pinfunction "2_2") (pintype "passive"))
      (node (ref "R8") (pin "2") (pinfunction "2_2") (pintype "passive"))
      (node (ref "R9") (pin "2") (pinfunction "2_2") (pintype "passive"))
      (node (ref "U1") (pin "2-7") (pinfunction "IOVDD_2-7") (pintype "passive"))
      (node (ref "U1") (pin "3-10") (pinfunction "IOVDD_3-10") (pintype "passive"))
      (node (ref "U1") (pin "4-21") (pinfunction "IOVDD_4-21") (pintype "passive"))
      (node (ref "U1") (pin "4-3") (pinfunction "IOVDD_4-3") (pintype "passive"))
      (node (ref "U3") (pin "3") (pinfunction "WP#_3") (pintype "passive"))
      (node (ref "U3") (pin "7") (pinfunction "HOLD#_7") (pintype "passive"))
      (node (ref "U3") (pin "8") (pinfunction "VCC_8") (pintype "passive"))
    )
    (net (code "40") (name "Net-(P2-LED-)") (class "Default")
      (node (ref "P2") (pin "3") (pinfunction "LED-_3") (pintype "passive"))
      (node (ref "P3") (pin "11") (pinfunction "LEDK1_11") (pintype "passive"))
      (node (ref "P3") (pin "12") (pinfunction "LEDK2_12") (pintype "passive"))
      (node (ref "P3") (pin "13") (pinfunction "LEDK3_13") (pintype "passive"))
      (node (ref "P3") (pin "14") (pinfunction "LEDK4_14") (pintype "passive"))
      (node (ref "R17") (pin "2") (pinfunction "2_2") (pintype "passive"))
    )
    (net (code "41") (name "Net-(R6-Pad1)") (class "Default")
      (node (ref "R6") (pin "1") (pinfunction "1_1") (pintype "passive"))
      (node (ref "S1") (pin "1") (pinfunction "1_1") (pintype "passive"))
    )
    (net (code "42") (name "Net-(R7-Pad1)") (class "Default")
      (node (ref "R7") (pin "1") (pinfunction "1_1") (pintype "passive"))
      (node (ref "S2") (pin "1") (pinfunction "1_1") (pintype "passive"))
    )
    (net (code "43") (name "Net-(R8-Pad1)") (class "Default")
      (node (ref "R8") (pin "1") (pinfunction "1_1") (pintype "passive"))
      (node (ref "S3") (pin "1") (pinfunction "1_1") (pintype "passive"))
    )
    (net (code "44") (name "Net-(R9-Pad1)") (class "Default")
      (node (ref "R9") (pin "1") (pinfunction "1_1") (pintype "passive"))
      (node (ref "S4") (pin "1") (pinfunction "1_1") (pintype "passive"))
    )
    (net (code "45") (name "Net-(U1-RX)") (class "Default")
      (node (ref "JP1") (pin "2") (pinfunction "2_2") (pintype "passive"))
      (node (ref "U1") (pin "4-15") (pinfunction "RX_4-15") (pintype "passive"))
    )
    (net (code "46") (name "Net-(U1-TX)") (class "Default")
      (node (ref "JP1") (pin "3") (pinfunction "3_3") (pintype "passive"))
      (node (ref "U1") (pin "4-16") (pinfunction "TX_4-16") (pintype "passive"))
    )
    (net (code "47") (name "Net-(U4-GP22)") (class "Default")
      (node (ref "R20") (pin "2") (pinfunction "2_2") (pintype "passive"))
      (node (ref "U4") (pin "29") (pinfunction "GP22_29") (pintype "passive"))
      (node (ref "U6") (pin "1") (pinfunction "G_1") (pintype "passive"))
    )
    (net (code "48") (name "VHIGH") (class "Default")
      (node (ref "C1") (pin "1") (pinfunction "1_1") (pintype "passive"))
      (node (ref "JP1") (pin "4") (pinfunction "4_4") (pintype "passive"))
      (node (ref "U1") (pin "2-4") (pinfunction "VHIGH_2-4") (pintype "passive"))
      (node (ref "U2") (pin "3") (pinfunction "VIN_3") (pintype "passive"))
      (node (ref "U4") (pin "39") (pinfunction "Vin_39") (pintype "passive"))
    )
    (net (code "49") (name "unconnected-(JP3-Pad4)") (class "Default")
      (node (ref "JP3") (pin "4") (pinfunction "4_4") (pintype "passive"))
    )
    (net (code "50") (name "unconnected-(P2-NC-Pad1)") (class "Default")
      (node (ref "P2") (pin "1") (pinfunction "NC_1") (pintype "passive"))
    )
    (net (code "51") (name "unconnected-(P2-NC-Pad14)") (class "Default")
      (node (ref "P2") (pin "14") (pinfunction "NC_14") (pintype "passive"))
    )
    (net (code "52") (name "unconnected-(P3-SDO-Pad7)") (class "Default")
      (node (ref "P3") (pin "7") (pinfunction "SDO_7") (pintype "passive"))
    )
    (net (code "53") (name "unconnected-(P3-XL-Pad15)") (class "Default")
      (node (ref "P3") (pin "15") (pinfunction "XL_15") (pintype "passive"))
    )
    (net (code "54") (name "unconnected-(P3-XR-Pad17)") (class "Default")
      (node (ref "P3") (pin "17") (pinfunction "XR_17") (pintype "passive"))
    )
    (net (code "55") (name "unconnected-(P3-YD-Pad18)") (class "Default")
      (node (ref "P3") (pin "18") (pinfunction "YD_18") (pintype "passive"))
    )
    (net (code "56") (name "unconnected-(P3-YU-Pad16)") (class "Default")
      (node (ref "P3") (pin "16") (pinfunction "YU_16") (pintype "passive"))
    )
    (net (code "57") (name "unconnected-(P4-Pad1)") (class "Default")
      (node (ref "P4") (pin "1") (pinfunction "1_1") (pintype "passive"))
    )
    (net (code "58") (name "unconnected-(P4-Pad3)") (class "Default")
      (node (ref "P4") (pin "3") (pinfunction "3_3") (pintype "passive"))
    )
    (net (code "59") (name "unconnected-(P4-Pad14)") (class "Default")
      (node (ref "P4") (pin "14") (pinfunction "14_14") (pintype "passive"))
    )
    (net (code "60") (name "unconnected-(U1-12M-Pad4-22)") (class "Default")
      (node (ref "U1") (pin "4-22") (pinfunction "12M_4-22") (pintype "passive"))
    )
    (net (code "61") (name "unconnected-(U1-ALE-Pad3-15)") (class "Default")
      (node (ref "U1") (pin "3-15") (pinfunction "ALE_3-15") (pintype "passive"))
    )
    (net (code "62") (name "unconnected-(U1-BCK-Pad4-19)") (class "Default")
      (node (ref "U1") (pin "4-19") (pinfunction "BCK_4-19") (pintype "passive"))
    )
    (net (code "63") (name "unconnected-(U1-CE-Pad4-4)") (class "Default")
      (node (ref "U1") (pin "4-4") (pinfunction "CE_4-4") (pintype "passive"))
    )
    (net (code "64") (name "unconnected-(U1-CLE-Pad3-14)") (class "Default")
      (node (ref "U1") (pin "3-14") (pinfunction "CLE_3-14") (pintype "passive"))
    )
    (net (code "65") (name "unconnected-(U1-D4-Pad2-13)") (class "Default")
      (node (ref "U1") (pin "2-13") (pinfunction "D4_2-13") (pintype "passive"))
    )
    (net (code "66") (name "unconnected-(U1-D5-Pad2-14)") (class "Default")
      (node (ref "U1") (pin "2-14") (pinfunction "D5_2-14") (pintype "passive"))
    )
    (net (code "67") (name "unconnected-(U1-D6-Pad2-15)") (class "Default")
      (node (ref "U1") (pin "2-15") (pinfunction "D6_2-15") (pintype "passive"))
    )
    (net (code "68") (name "unconnected-(U1-D7-Pad2-16)") (class "Default")
      (node (ref "U1") (pin "2-16") (pinfunction "D7_2-16") (pintype "passive"))
    )
    (net (code "69") (name "unconnected-(U1-DBG-Pad3-17)") (class "Default")
      (node (ref "U1") (pin "3-17") (pinfunction "DBG_3-17") (pintype "passive"))
    )
    (net (code "70") (name "unconnected-(U1-DBGQR-Pad4-13)") (class "Default")
      (node (ref "U1") (pin "4-13") (pinfunction "DBGQR_4-13") (pintype "passive"))
    )
    (net (code "71") (name "unconnected-(U1-DI-Pad4-17)") (class "Default")
      (node (ref "U1") (pin "4-17") (pinfunction "DI_4-17") (pintype "passive"))
    )
    (net (code "72") (name "unconnected-(U1-DO-Pad4-18)") (class "Default")
      (node (ref "U1") (pin "4-18") (pinfunction "DO_4-18") (pintype "passive"))
    )
    (net (code "73") (name "unconnected-(U1-E-RXP-Pad3-7)") (class "Default")
      (node (ref "U1") (pin "3-7") (pinfunction "E-RXP_3-7") (pintype "passive"))
    )
    (net (code "74") (name "unconnected-(U1-E-TXN-Pad3-11)") (class "Default")
      (node (ref "U1") (pin "3-11") (pinfunction "E-TXN_3-11") (pintype "passive"))
    )
    (net (code "75") (name "unconnected-(U1-E-TXP-Pad3-9)") (class "Default")
      (node (ref "U1") (pin "3-9") (pinfunction "E-TXP_3-9") (pintype "passive"))
    )
    (net (code "76") (name "unconnected-(U1-FRM-Pad4-20)") (class "Default")
      (node (ref "U1") (pin "4-20") (pinfunction "FRM_4-20") (pintype "passive"))
    )
    (net (code "77") (name "unconnected-(U1-FVDD-Pad2-6)") (class "Default")
      (node (ref "U1") (pin "2-6") (pinfunction "FVDD_2-6") (pintype "passive"))
    )
    (net (code "78") (name "unconnected-(U1-GBUF-Pad1-16)") (class "Default")
      (node (ref "U1") (pin "1-16") (pinfunction "GBUF_1-16") (pintype "passive"))
    )
    (net (code "79") (name "unconnected-(U1-GPIO1-15-Pad3-8)") (class "Default")
      (node (ref "U1") (pin "3-8") (pinfunction "GPIO1-15_3-8") (pintype "passive"))
    )
    (net (code "80") (name "unconnected-(U1-L1-3-Pad1-3)") (class "Default")
      (node (ref "U1") (pin "1-3") (pinfunction "L1-3_1-3") (pintype "passive"))
    )
    (net (code "81") (name "unconnected-(U1-L2-1-Pad1-2)") (class "Default")
      (node (ref "U1") (pin "1-2") (pinfunction "L2-1_1-2") (pintype "passive"))
    )
    (net (code "82") (name "unconnected-(U1-L2-2-Pad1-1)") (class "Default")
      (node (ref "U1") (pin "1-1") (pinfunction "L2-2_1-1") (pintype "passive"))
    )
    (net (code "83") (name "unconnected-(U1-L3-1-Pad1-5)") (class "Default")
      (node (ref "U1") (pin "1-5") (pinfunction "L3-1_1-5") (pintype "passive"))
    )
    (net (code "84") (name "unconnected-(U1-L3-2-Pad1-4)") (class "Default")
      (node (ref "U1") (pin "1-4") (pinfunction "L3-2_1-4") (pintype "passive"))
    )
    (net (code "85") (name "unconnected-(U1-LEFT-Pad1-17)") (class "Default")
      (node (ref "U1") (pin "1-17") (pinfunction "LEFT_1-17") (pintype "passive"))
    )
    (net (code "86") (name "unconnected-(U1-LI-L-1-1-Pad1-7)") (class "Default")
      (node (ref "U1") (pin "1-7") (pinfunction "LI-L-1-1_1-7") (pintype "passive"))
    )
    (net (code "87") (name "unconnected-(U1-LI-R-1-2-Pad1-6)") (class "Default")
      (node (ref "U1") (pin "1-6") (pinfunction "LI-R-1-2_1-6") (pintype "passive"))
    )
    (net (code "88") (name "unconnected-(U1-MIS01-Pad2-22)") (class "Default")
      (node (ref "U1") (pin "2-22") (pinfunction "MIS01_2-22") (pintype "passive"))
    )
    (net (code "89") (name "unconnected-(U1-MOSI1-Pad4-1)") (class "Default")
      (node (ref "U1") (pin "4-1") (pinfunction "MOSI1_4-1") (pintype "passive"))
    )
    (net (code "90") (name "unconnected-(U1-PBTN-Pad3-19)") (class "Default")
      (node (ref "U1") (pin "3-19") (pinfunction "PBTN_3-19") (pintype "passive"))
    )
    (net (code "91") (name "unconnected-(U1-PWM-Pad1-22)") (class "Default")
      (node (ref "U1") (pin "1-22") (pinfunction "PWM_1-22") (pintype "passive"))
    )
    (net (code "92") (name "unconnected-(U1-Pad1-15)") (class "Default")
      (node (ref "U1") (pin "1-15") (pintype "passive"))
    )
    (net (code "93") (name "unconnected-(U1-RCAP-Pad1-12)") (class "Default")
      (node (ref "U1") (pin "1-12") (pinfunction "RCAP_1-12") (pintype "passive"))
    )
    (net (code "94") (name "unconnected-(U1-RD-Pad2-18)") (class "Default")
      (node (ref "U1") (pin "2-18") (pinfunction "RD_2-18") (pintype "passive"))
    )
    (net (code "95") (name "unconnected-(U1-RDY-Pad2-17)") (class "Default")
      (node (ref "U1") (pin "2-17") (pinfunction "RDY_2-17") (pintype "passive"))
    )
    (net (code "96") (name "unconnected-(U1-RFN-Pad1-9)") (class "Default")
      (node (ref "U1") (pin "1-9") (pinfunction "RFN_1-9") (pintype "passive"))
    )
    (net (code "97") (name "unconnected-(U1-RFP-Pad1-10)") (class "Default")
      (node (ref "U1") (pin "1-10") (pinfunction "RFP_1-10") (pintype "passive"))
    )
    (net (code "98") (name "unconnected-(U1-RIGHT-Pad1-14)") (class "Default")
      (node (ref "U1") (pin "1-14") (pinfunction "RIGHT_1-14") (pintype "passive"))
    )
    (net (code "99") (name "unconnected-(U1-RTCVDD-Pad3-20)") (class "Default")
      (node (ref "U1") (pin "3-20") (pinfunction "RTCVDD_3-20") (pintype "passive"))
    )
    (net (code "100") (name "unconnected-(U1-SCLK1-Pad2-20)") (class "Default")
      (node (ref "U1") (pin "2-20") (pinfunction "SCLK1_2-20") (pintype "passive"))
    )
    (net (code "101") (name "unconnected-(U1-SPIN-Pad3-12)") (class "Default")
      (node (ref "U1") (pin "3-12") (pinfunction "SPIN_3-12") (pintype "passive"))
    )
    (net (code "102") (name "unconnected-(U1-SPOUT-Pad3-13)") (class "Default")
      (node (ref "U1") (pin "3-13") (pinfunction "SPOUT_3-13") (pintype "passive"))
    )
    (net (code "103") (name "unconnected-(U1-TCK-Pad4-12)") (class "Default")
      (node (ref "U1") (pin "4-12") (pinfunction "TCK_4-12") (pintype "passive"))
    )
    (net (code "104") (name "unconnected-(U1-TDI-Pad4-10)") (class "Default")
      (node (ref "U1") (pin "4-10") (pinfunction "TDI_4-10") (pintype "passive"))
    )
    (net (code "105") (name "unconnected-(U1-TDO-Pad4-11)") (class "Default")
      (node (ref "U1") (pin "4-11") (pinfunction "TDO_4-11") (pintype "passive"))
    )
    (net (code "106") (name "unconnected-(U1-TMS-Pad4-9)") (class "Default")
      (node (ref "U1") (pin "4-9") (pinfunction "TMS_4-9") (pintype "passive"))
    )
    (net (code "107") (name "unconnected-(U1-TST-Pad3-18)") (class "Default")
      (node (ref "U1") (pin "3-18") (pinfunction "TST_3-18") (pintype "passive"))
    )
    (net (code "108") (name "unconnected-(U1-USBN-Pad1-20)") (class "Default")
      (node (ref "U1") (pin "1-20") (pinfunction "USBN_1-20") (pintype "passive"))
    )
    (net (code "109") (name "unconnected-(U1-USBP-Pad1-19)") (class "Default")
      (node (ref "U1") (pin "1-19") (pinfunction "USBP_1-19") (pintype "passive"))
    )
    (net (code "110") (name "unconnected-(U1-WR-Pad4-2)") (class "Default")
      (node (ref "U1") (pin "4-2") (pinfunction "WR_4-2") (pintype "passive"))
    )
    (net (code "111") (name "unconnected-(U1-XCS1-Pad2-19)") (class "Default")
      (node (ref "U1") (pin "2-19") (pinfunction "XCS1_2-19") (pintype "passive"))
    )
    (net (code "112") (name "unconnected-(U1-XT0-Pad2-1)") (class "Default")
      (node (ref "U1") (pin "2-1") (pinfunction "XT0_2-1") (pintype "passive"))
    )
    (net (code "113") (name "unconnected-(U1-XTI-Pad2-2)") (class "Default")
      (node (ref "U1") (pin "2-2") (pinfunction "XTI_2-2") (pintype "passive"))
    )
    (net (code "114") (name "unconnected-(U1-XTIR-Pad3-22)") (class "Default")
      (node (ref "U1") (pin "3-22") (pinfunction "XTIR_3-22") (pintype "passive"))
    )
    (net (code "115") (name "unconnected-(U1-XTOR-Pad3-21)") (class "Default")
      (node (ref "U1") (pin "3-21") (pinfunction "XTOR_3-21") (pintype "passive"))
    )
    (net (code "116") (name "unconnected-(U4-3V3-Pad36)") (class "Default")
      (node (ref "U4") (pin "36") (pinfunction "3V3_36") (pintype "passive"))
    )
    (net (code "117") (name "unconnected-(U4-3V3-Pad41)") (class "Default")
      (node (ref "U4") (pin "41") (pinfunction "3V3_41") (pintype "passive"))
    )
    (net (code "118") (name "unconnected-(U4-GND-Pad44)") (class "Default")
      (node (ref "U4") (pin "44") (pinfunction "GND_44") (pintype "passive"))
    )
    (net (code "119") (name "unconnected-(U4-GP3-Pad5)") (class "Default")
      (node (ref "U4") (pin "5") (pinfunction "GP3_5") (pintype "passive"))
    )
    (net (code "120") (name "unconnected-(U4-GP4-Pad6)") (class "Default")
      (node (ref "U4") (pin "6") (pinfunction "GP4_6") (pintype "passive"))
    )
    (net (code "121") (name "unconnected-(U4-GP5-Pad7)") (class "Default")
      (node (ref "U4") (pin "7") (pinfunction "GP5_7") (pintype "passive"))
    )
    (net (code "122") (name "unconnected-(U4-GP6-Pad9)") (class "Default")
      (node (ref "U4") (pin "9") (pinfunction "GP6_9") (pintype "passive"))
    )
    (net (code "123") (name "unconnected-(U4-GP7-Pad10)") (class "Default")
      (node (ref "U4") (pin "10") (pinfunction "GP7_10") (pintype "passive"))
    )
    (net (code "124") (name "unconnected-(U4-GP12-Pad16)") (class "Default")
      (node (ref "U4") (pin "16") (pinfunction "GP12_16") (pintype "passive"))
    )
    (net (code "125") (name "unconnected-(U4-GP13-Pad17)") (class "Default")
      (node (ref "U4") (pin "17") (pinfunction "GP13_17") (pintype "passive"))
    )
    (net (code "126") (name "unconnected-(U4-GP14-Pad19)") (class "Default")
      (node (ref "U4") (pin "19") (pinfunction "GP14_19") (pintype "passive"))
    )
    (net (code "127") (name "unconnected-(U4-GP15-Pad20)") (class "Default")
      (node (ref "U4") (pin "20") (pinfunction "GP15_20") (pintype "passive"))
    )
    (net (code "128") (name "unconnected-(U4-GP19-Pad25)") (class "Default")
      (node (ref "U4") (pin "25") (pinfunction "GP19_25") (pintype "passive"))
    )
    (net (code "129") (name "unconnected-(U4-GP20-Pad26)") (class "Default")
      (node (ref "U4") (pin "26") (pinfunction "GP20_26") (pintype "passive"))
    )
    (net (code "130") (name "unconnected-(U4-GP21-Pad27)") (class "Default")
      (node (ref "U4") (pin "27") (pinfunction "GP21_27") (pintype "passive"))
    )
    (net (code "131") (name "unconnected-(U4-GP23-Pad37)") (class "Default")
      (node (ref "U4") (pin "37") (pinfunction "GP23_37") (pintype "passive"))
    )
    (net (code "132") (name "unconnected-(U4-GP27-Pad32)") (class "Default")
      (node (ref "U4") (pin "32") (pinfunction "GP27_32") (pintype "passive"))
    )
    (net (code "133") (name "unconnected-(U4-GP28-Pad34)") (class "Default")
      (node (ref "U4") (pin "34") (pinfunction "GP28_34") (pintype "passive"))
    )
    (net (code "134") (name "unconnected-(U4-GP29-Pad35)") (class "Default")
      (node (ref "U4") (pin "35") (pinfunction "GP29_35") (pintype "passive"))
    )
    (net (code "135") (name "unconnected-(U4-RUN-Pad30)") (class "Default")
      (node (ref "U4") (pin "30") (pinfunction "RUN_30") (pintype "passive"))
    )
    (net (code "136") (name "unconnected-(U4-SWCLK-Pad43)") (class "Default")
      (node (ref "U4") (pin "43") (pinfunction "SWCLK_43") (pintype "passive"))
    )
    (net (code "137") (name "unconnected-(U4-SWDIO-Pad42)") (class "Default")
      (node (ref "U4") (pin "42") (pinfunction "SWDIO_42") (pintype "passive"))
    )
    (net (code "138") (name "unconnected-(U4-Vout-Pad40)") (class "Default")
      (node (ref "U4") (pin "40") (pinfunction "Vout_40") (pintype "passive"))
    )
    (net (code "139") (name "unconnected-(U5-Y7-Pad4)") (class "Default")
      (node (ref "U5") (pin "4") (pinfunction "Y7_4") (pintype "passive"))
    )
    (net (code "140") (name "unconnected-(VR1-2-Pad4)") (class "Default")
      (node (ref "VR1") (pin "4") (pinfunction "2_4") (pintype "passive"))
    )
    (net (code "141") (name "unconnected-(VR1-Pad5)") (class "Default")
      (node (ref "VR1") (pin "5") (pinfunction "5_5") (pintype "passive"))
    )
    (net (code "142") (name "unconnected-(VR1-Pad6)") (class "Default")
      (node (ref "VR1") (pin "6") (pinfunction "6_6") (pintype "passive"))
    )
    (net (code "143") (name "unconnected-(VR2-2-Pad4)") (class "Default")
      (node (ref "VR2") (pin "4") (pinfunction "2_4") (pintype "passive"))
    )
    (net (code "144") (name "unconnected-(VR2-Pad5)") (class "Default")
      (node (ref "VR2") (pin "5") (pinfunction "5_5") (pintype "passive"))
    )
    (net (code "145") (name "unconnected-(VR2-Pad6)") (class "Default")
      (node (ref "VR2") (pin "6") (pinfunction "6_6") (pintype "passive"))
    )
    (net (code "146") (name "unconnected-(VR3-2-Pad4)") (class "Default")
      (node (ref "VR3") (pin "4") (pinfunction "2_4") (pintype "passive"))
    )
    (net (code "147") (name "unconnected-(VR3-Pad5)") (class "Default")
      (node (ref "VR3") (pin "5") (pinfunction "5_5") (pintype "passive"))
    )
    (net (code "148") (name "unconnected-(VR3-Pad6)") (class "Default")
      (node (ref "VR3") (pin "6") (pinfunction "6_6") (pintype "passive"))
    )
    (net (code "149") (name "unconnected-(VR4-2-Pad4)") (class "Default")
      (node (ref "VR4") (pin "4") (pinfunction "2_4") (pintype "passive"))
    )
    (net (code "150") (name "unconnected-(VR4-Pad5)") (class "Default")
      (node (ref "VR4") (pin "5") (pinfunction "5_5") (pintype "passive"))
    )
    (net (code "151") (name "unconnected-(VR4-Pad6)") (class "Default")
      (node (ref "VR4") (pin "6") (pinfunction "6_6") (pintype "passive"))
    )
    (net (code "152") (name "unconnected-(VR5-2-Pad4)") (class "Default")
      (node (ref "VR5") (pin "4") (pinfunction "2_4") (pintype "passive"))
    )
    (net (code "153") (name "unconnected-(VR5-Pad5)") (class "Default")
      (node (ref "VR5") (pin "5") (pinfunction "5_5") (pintype "passive"))
    )
    (net (code "154") (name "unconnected-(VR5-Pad6)") (class "Default")
      (node (ref "VR5") (pin "6") (pinfunction "6_6") (pintype "passive"))
    )
    (net (code "155") (name "unconnected-(VR6-2-Pad4)") (class "Default")
      (node (ref "VR6") (pin "4") (pinfunction "2_4") (pintype "passive"))
    )
    (net (code "156") (name "unconnected-(VR6-Pad5)") (class "Default")
      (node (ref "VR6") (pin "5") (pinfunction "5_5") (pintype "passive"))
    )
    (net (code "157") (name "unconnected-(VR6-Pad6)") (class "Default")
      (node (ref "VR6") (pin "6") (pinfunction "6_6") (pintype "passive"))
    )
    (net (code "158") (name "unconnected-(VR7-2-Pad4)") (class "Default")
      (node (ref "VR7") (pin "4") (pinfunction "2_4") (pintype "passive"))
    )
    (net (code "159") (name "unconnected-(VR7-Pad5)") (class "Default")
      (node (ref "VR7") (pin "5") (pinfunction "5_5") (pintype "passive"))
    )
    (net (code "160") (name "unconnected-(VR7-Pad6)") (class "Default")
      (node (ref "VR7") (pin "6") (pinfunction "6_6") (pintype "passive"))
    )
  )
)
